# Thermistor.net
KiCad netlist of a schematic drawn in EAGLE
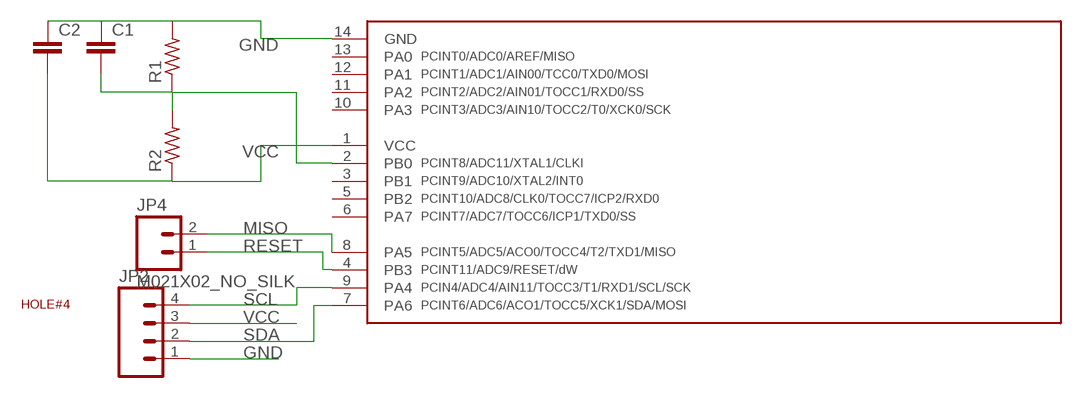
[diagram p0: schematic, sheet 1]

(export (version "E")
  (design (tool "Eeschema 10.0.6"))
  (components
    (comp (ref "C1")
      (value "C-EUC0805")
      (footprint "eagle-import:C0805")
      (libsource (lib "eagle-import") (part "C-EUC0805"))
    )
    (comp (ref "C2")
      (value "C-EUC0805")
      (footprint "eagle-import:C0805")
      (libsource (lib "eagle-import") (part "C-EUC0805"))
    )
    (comp (ref "JP2")
      (value "M041X04_NO_SILK")
      (footprint "eagle-import:1X04_NO_SILK")
      (libsource (lib "eagle-import") (part "M041X04_NO_SILK"))
    )
    (comp (ref "JP4")
      (value "M021X02_NO_SILK")
      (footprint "eagle-import:1X02_NO_SILK")
      (libsource (lib "eagle-import") (part "M021X02_NO_SILK"))
    )
    (comp (ref "R1")
      (value "R-US_R0805")
      (footprint "eagle-import:R0805")
      (libsource (lib "eagle-import") (part "R-US_R0805"))
    )
    (comp (ref "R2")
      (value "R-US_R0805")
      (footprint "eagle-import:R0805")
      (libsource (lib "eagle-import") (part "R-US_R0805"))
    )
    (comp (ref "U$1")
      (value "TINY841")
      (footprint "eagle-import:SOIC14")
      (libsource (lib "eagle-import") (part "TINY841"))
    )
    (comp (ref "U$2")
      (value "HOLE#4")
      (footprint "eagle-import:HOLE-#4")
      (libsource (lib "eagle-import") (part "HOLE#4"))
    )
  )
  (nets
    (net (code "1") (name "/GND") (class "Default")
      (node (ref "C1") (pin "1") (pinfunction "1_1") (pintype "passive"))
      (node (ref "C2") (pin "1") (pinfunction "1_1") (pintype "passive"))
      (node (ref "JP2") (pin "1") (pinfunction "1_1") (pintype "passive"))
      (node (ref "R1") (pin "2") (pinfunction "2_2") (pintype "passive"))
      (node (ref "U$1") (pin "14") (pinfunction "GND_14") (pintype "bidirectional"))
    )
    (net (code "2") (name "/MISO") (class "Default")
      (node (ref "JP4") (pin "2") (pinfunction "2_2") (pintype "passive"))
      (node (ref "U$1") (pin "8") (pinfunction "PA5_8") (pintype "bidirectional"))
    )
    (net (code "3") (name "/RESET") (class "Default")
      (node (ref "JP4") (pin "1") (pinfunction "1_1") (pintype "passive"))
      (node (ref "U$1") (pin "4") (pinfunction "PB3_4") (pintype "bidirectional"))
    )
    (net (code "4") (name "/SCL") (class "Default")
      (node (ref "JP2") (pin "4") (pinfunction "4_4") (pintype "passive"))
      (node (ref "U$1") (pin "9") (pinfunction "PA4_9") (pintype "bidirectional"))
    )
    (net (code "5") (name "/SDA") (class "Default")
      (node (ref "JP2") (pin "2") (pinfunction "2_2") (pintype "passive"))
      (node (ref "U$1") (pin "7") (pinfunction "PA6_7") (pintype "bidirectional"))
    )
    (net (code "6") (name "/VCC") (class "Default")
      (node (ref "C2") (pin "2") (pinfunction "2_2") (pintype "passive"))
      (node (ref "JP2") (pin "3") (pinfunction "3_3") (pintype "passive"))
      (node (ref "R2") (pin "1") (pinfunction "1_1") (pintype "passive"))
      (node (ref "U$1") (pin "1") (pinfunction "VCC_1") (pintype "bidirectional"))
    )
    (net (code "7") (name "Net-(U$1-PB0)") (class "Default")
      (node (ref "C1") (pin "2") (pinfunction "2_2") (pintype "passive"))
      (node (ref "R1") (pin "1") (pinfunction "1_1") (pintype "passive"))
      (node (ref "R2") (pin "2") (pinfunction "2_2") (pintype "passive"))
      (node (ref "U$1") (pin "2") (pinfunction "PB0_2") (pintype "bidirectional"))
    )
    (net (code "8") (name "unconnected-(U$1-PA0-Pad13)") (class "Default")
      (node (ref "U$1") (pin "13") (pinfunction "PA0_13") (pintype "bidirectional"))
    )
    (net (code "9") (name "unconnected-(U$1-PA1-Pad12)") (class "Default")
      (node (ref "U$1") (pin "12") (pinfunction "PA1_12") (pintype "bidirectional"))
    )
    (net (code "10") (name "unconnected-(U$1-PA2-Pad11)") (class "Default")
      (node (ref "U$1") (pin "11") (pinfunction "PA2_11") (pintype "bidirectional"))
    )
    (net (code "11") (name "unconnected-(U$1-PA3-Pad10)") (class "Default")
      (node (ref "U$1") (pin "10") (pinfunction "PA3_10") (pintype "bidirectional"))
    )
    (net (code "12") (name "unconnected-(U$1-PA7-Pad6)") (class "Default")
      (node (ref "U$1") (pin "6") (pinfunction "PA7_6") (pintype "bidirectional"))
    )
    (net (code "13") (name "unconnected-(U$1-PB1-Pad3)") (class "Default")
      (node (ref "U$1") (pin "3") (pinfunction "PB1_3") (pintype "bidirectional"))
    )
    (net (code "14") (name "unconnected-(U$1-PB2-Pad5)") (class "Default")
      (node (ref "U$1") (pin "5") (pinfunction "PB2_5") (pintype "bidirectional"))
    )
    (net (code "15") (name "unconnected-(U$2-HOLE-PadP$1)") (class "Default")
      (node (ref "U$2") (pin "P$1") (pinfunction "HOLE_P$1") (pintype "bidirectional"))
    )
  )
)
